# Power_Supply.net
KiCad netlist of a schematic drawn in Altium Designer
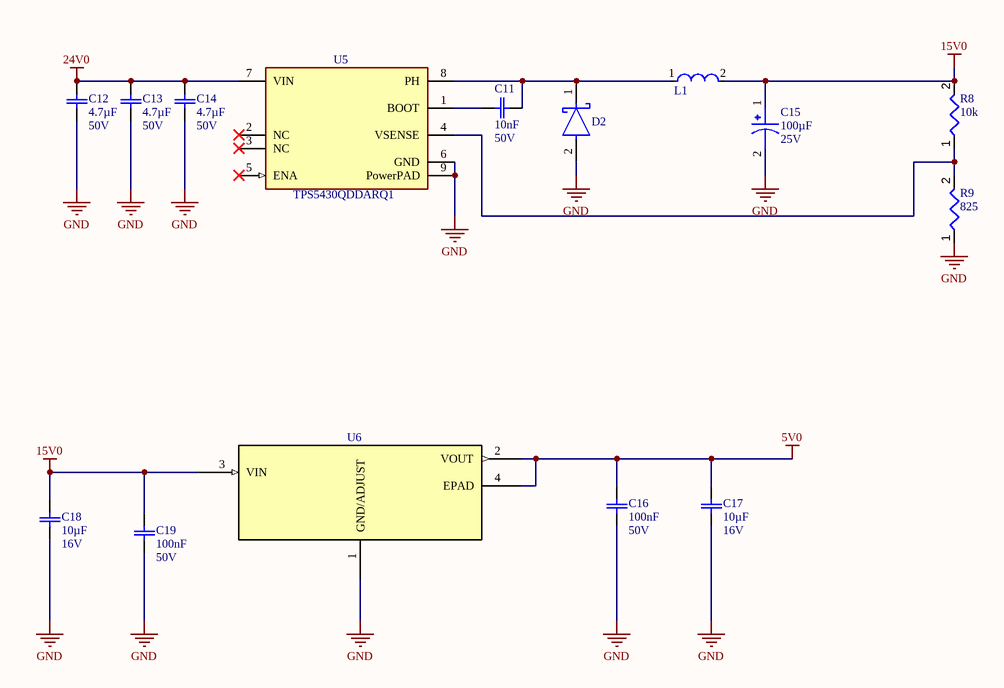
[diagram p0: Power_Supply.SchDoc]

(export (version "E")
  (design (tool "Eeschema 10.0.6"))
  (components
    (comp (ref "C11")
      (value "10nF")
      (footprint "Generic Ceramic 0603 CAP")
      (fields
        (field (name "VOLTAGE RATING") "50V")
        (field (name "Comment") "CAP-MLCC_SMD-0603_MR-GCM_n_10nF_50V_10%_COG")
      )
      (libsource (lib "Paulo Peixoto") (part "CAP_Ceramic"))
    )
    (comp (ref "C12")
      (value "4.7µF")
      (footprint "Generic Ceramic 0805 CAP")
      (fields
        (field (name "VOLTAGE RATING") "50V")
        (field (name "TOLERANCE") "10%")
        (field (name "Comment") "CAP-MLCC_SMD-0805_TDK-CGA_u_4.7uF_V_10%_X8R")
      )
      (libsource (lib "Paulo Peixoto") (part "CAP_Ceramic"))
    )
    (comp (ref "C13")
      (value "4.7µF")
      (footprint "Generic Ceramic 0805 CAP")
      (fields
        (field (name "VOLTAGE RATING") "50V")
        (field (name "TOLERANCE") "10%")
        (field (name "Comment") "CAP-MLCC_SMD-0805_TDK-CGA_u_4.7uF_V_10%_X8R")
      )
      (libsource (lib "Paulo Peixoto") (part "CAP_Ceramic"))
    )
    (comp (ref "C14")
      (value "4.7µF")
      (footprint "Generic Ceramic 0805 CAP")
      (fields
        (field (name "VOLTAGE RATING") "50V")
        (field (name "TOLERANCE") "10%")
        (field (name "Comment") "CAP-MLCC_SMD-0805_TDK-CGA_u_4.7uF_V_10%_X8R")
      )
      (libsource (lib "Paulo Peixoto") (part "CAP_Ceramic"))
    )
    (comp (ref "C15")
      (value "100µF")
      (footprint "FP-FKE-MFG")
      (fields
        (field (name "VOLTAGE RATING") "25V")
        (field (name "MANUFACTURER PART NUMBER") "EEE-FK1H101GP")
        (field (name "Comment") "CAP_ELEC_SMD_PNS__EEE_u_100uF_25V_20%")
      )
      (libsource (lib "Paulo Peixoto") (part "Generic_Electrolytic_Cap"))
    )
    (comp (ref "C16")
      (value "100nF")
      (footprint "Generic Ceramic 0603 CAP")
      (fields
        (field (name "VOLTAGE RATING") "50V")
        (field (name "Comment") "CAP-MLCC_SMD-0603_MR-GCM_u_0.1uF_50V_10%_X8L")
      )
      (libsource (lib "Paulo Peixoto") (part "CAP_Ceramic"))
    )
    (comp (ref "C17")
      (value "10µF")
      (footprint "Generic Ceramic 0805 CAP")
      (fields
        (field (name "VOLTAGE RATING") "16V")
        (field (name "TOLERANCE") "20%")
        (field (name "Comment") "CAP-MLCC_SMD-0805_TDK-CGA_u_10uF_16V_20%_X7S")
      )
      (libsource (lib "Paulo Peixoto") (part "CAP_Ceramic"))
    )
    (comp (ref "C18")
      (value "10µF")
      (footprint "Generic Ceramic 0805 CAP")
      (fields
        (field (name "VOLTAGE RATING") "16V")
        (field (name "TOLERANCE") "20%")
        (field (name "Comment") "CAP-MLCC_SMD-0805_TDK-CGA_u_10uF_16V_20%_X7S")
      )
      (libsource (lib "Paulo Peixoto") (part "CAP_Ceramic"))
    )
    (comp (ref "C19")
      (value "100nF")
      (footprint "Generic Ceramic 0603 CAP")
      (fields
        (field (name "VOLTAGE RATING") "50V")
        (field (name "Comment") "CAP-MLCC_SMD-0603_MR-GCM_u_0.1uF_50V_10%_X8L")
      )
      (libsource (lib "Paulo Peixoto") (part "CAP_Ceramic"))
    )
    (comp (ref "D2")
      (value "MBRA340T3G")
      (footprint "ONSC-SMA-2-403D-02_F_V")
      (description "Diode, Schottky Barrier, Vr 40V, If 3A, Pkg SMA, Vf 0.45V, Tj +150degc, Cs 100A, Ir 15mA")
      (libsource (lib "Paulo Peixoto") (part "Generic_Shottky_Diode"))
    )
    (comp (ref "L1")
      (value "SRR1260-150M")
      (footprint "FP-SRR1260-MFG")
      (description "FIXED IND 15UH 5A 27 MOHM SMD")
      (fields (field (name "TOLERANCE") "20%"))
      (libsource (lib "Altium Content Vault") (part "725321dda6339637d4d059423bc1c3c"))
    )
    (comp (ref "R8")
      (value "10k")
      (footprint "Generic_0603_RES")
      (fields
        (field (name "POWER") "100mW")
        (field (name "TOLERANCE") "1%")
        (field (name "Comment") "RES-TK_SMD-0603_VIS-CRCW_K_10K_1/10W_1%")
      )
      (libsource (lib "Paulo Peixoto") (part "Res"))
    )
    (comp (ref "R9")
      (value "825")
      (footprint "Generic_0603_RES")
      (fields
        (field (name "POWER") "100mW")
        (field (name "TOLERANCE") "1%")
        (field (name "Comment") "RES-TK_SMD-0603_VIS-CRCW_R_825R_1/10W_1%")
      )
      (libsource (lib "Paulo Peixoto") (part "Res"))
    )
    (comp (ref "U5")
      (value "TPS5430QDDARQ1")
      (footprint "FP-DDA0008J-IPC_B")
      (description "Automotive 5.5V to 36V, 500kHz Fixed Frequency 3A Buck Converter 8-SO PowerPAD -40 to 125")
      (libsource (lib "Paulo Peixoto") (part "525499b92f9124456ec0db766472914"))
    )
    (comp (ref "U6")
      (value "AMS1117-5.0")
      (footprint "AMS1117-3.3-Footprint-1")
      (description "LDO Regulator Pos 5V 1A 4-Pin(3+Tab) SOT-223 / 1A LOW DROPOUT VOLTAGE REGULATOR")
      (libsource (lib "Paulo Peixoto") (part "AMS1117-3.3-Symbol-1"))
    )
  )
  (nets
    (net (code "1") (name "5V0") (class "Default")
      (node (ref "C16") (pin "2") (pinfunction "2_2") (pintype "passive"))
      (node (ref "C17") (pin "2") (pinfunction "2_2") (pintype "passive"))
      (node (ref "U6") (pin "2") (pinfunction "VOUT_2") (pintype "output"))
      (node (ref "U6") (pin "4") (pinfunction "EPAD_4") (pintype "power_in"))
    )
    (net (code "2") (name "15V0") (class "Default")
      (node (ref "C15") (pin "1") (pinfunction "1_1") (pintype "passive"))
      (node (ref "C18") (pin "2") (pinfunction "2_2") (pintype "passive"))
      (node (ref "C19") (pin "2") (pinfunction "2_2") (pintype "passive"))
      (node (ref "L1") (pin "2") (pinfunction "2_2") (pintype "passive"))
      (node (ref "R8") (pin "2") (pinfunction "2_2") (pintype "passive"))
      (node (ref "U6") (pin "3") (pinfunction "VIN_3") (pintype "input"))
    )
    (net (code "3") (name "24V0") (class "Default")
      (node (ref "C12") (pin "2") (pinfunction "2_2") (pintype "passive"))
      (node (ref "C13") (pin "2") (pinfunction "2_2") (pintype "passive"))
      (node (ref "C14") (pin "2") (pinfunction "2_2") (pintype "passive"))
      (node (ref "U5") (pin "7") (pinfunction "VIN_7") (pintype "power_in"))
    )
    (net (code "4") (name "GND") (class "Default")
      (node (ref "C12") (pin "1") (pinfunction "1_1") (pintype "passive"))
      (node (ref "C13") (pin "1") (pinfunction "1_1") (pintype "passive"))
      (node (ref "C14") (pin "1") (pinfunction "1_1") (pintype "passive"))
      (node (ref "C15") (pin "2") (pinfunction "2_2") (pintype "passive"))
      (node (ref "C16") (pin "1") (pinfunction "1_1") (pintype "passive"))
      (node (ref "C17") (pin "1") (pinfunction "1_1") (pintype "passive"))
      (node (ref "C18") (pin "1") (pinfunction "1_1") (pintype "passive"))
      (node (ref "C19") (pin "1") (pinfunction "1_1") (pintype "passive"))
      (node (ref "D2") (pin "2") (pinfunction "A_2") (pintype "passive"))
      (node (ref "R9") (pin "1") (pinfunction "1_1") (pintype "passive"))
      (node (ref "U5") (pin "6") (pinfunction "GND_6") (pintype "power_in"))
      (node (ref "U5") (pin "9") (pinfunction "PowerPAD_9") (pintype "power_in"))
      (node (ref "U6") (pin "1") (pinfunction "GND/ADJUST_1") (pintype "power_in"))
    )
    (net (code "5") (name "Net-(D2-C)") (class "Default")
      (node (ref "C11") (pin "1") (pinfunction "1_1") (pintype "passive"))
      (node (ref "D2") (pin "1") (pinfunction "C_1") (pintype "passive"))
      (node (ref "L1") (pin "1") (pinfunction "1_1") (pintype "passive"))
      (node (ref "U5") (pin "8") (pinfunction "PH_8") (pintype "passive"))
    )
    (net (code "6") (name "Net-(U5-BOOT)") (class "Default")
      (node (ref "C11") (pin "2") (pinfunction "2_2") (pintype "passive"))
      (node (ref "U5") (pin "1") (pinfunction "BOOT_1") (pintype "passive"))
    )
    (net (code "7") (name "Net-(U5-VSENSE)") (class "Default")
      (node (ref "R8") (pin "1") (pinfunction "1_1") (pintype "passive"))
      (node (ref "R9") (pin "2") (pinfunction "2_2") (pintype "passive"))
      (node (ref "U5") (pin "4") (pinfunction "VSENSE_4") (pintype "power_in"))
    )
    (net (code "8") (name "unconnected-(U5-ENA-Pad5)") (class "Default")
      (node (ref "U5") (pin "5") (pinfunction "ENA_5") (pintype "input+no_connect"))
    )
    (net (code "9") (name "unconnected-(U5-NC-Pad2)") (class "Default")
      (node (ref "U5") (pin "2") (pinfunction "NC_2") (pintype "passive+no_connect"))
    )
    (net (code "10") (name "unconnected-(U5-NC-Pad3)") (class "Default")
      (node (ref "U5") (pin "3") (pinfunction "NC_3") (pintype "passive+no_connect"))
    )
  )
)
